# detect-UHF.net
KiCad netlist of a schematic drawn in EAGLE
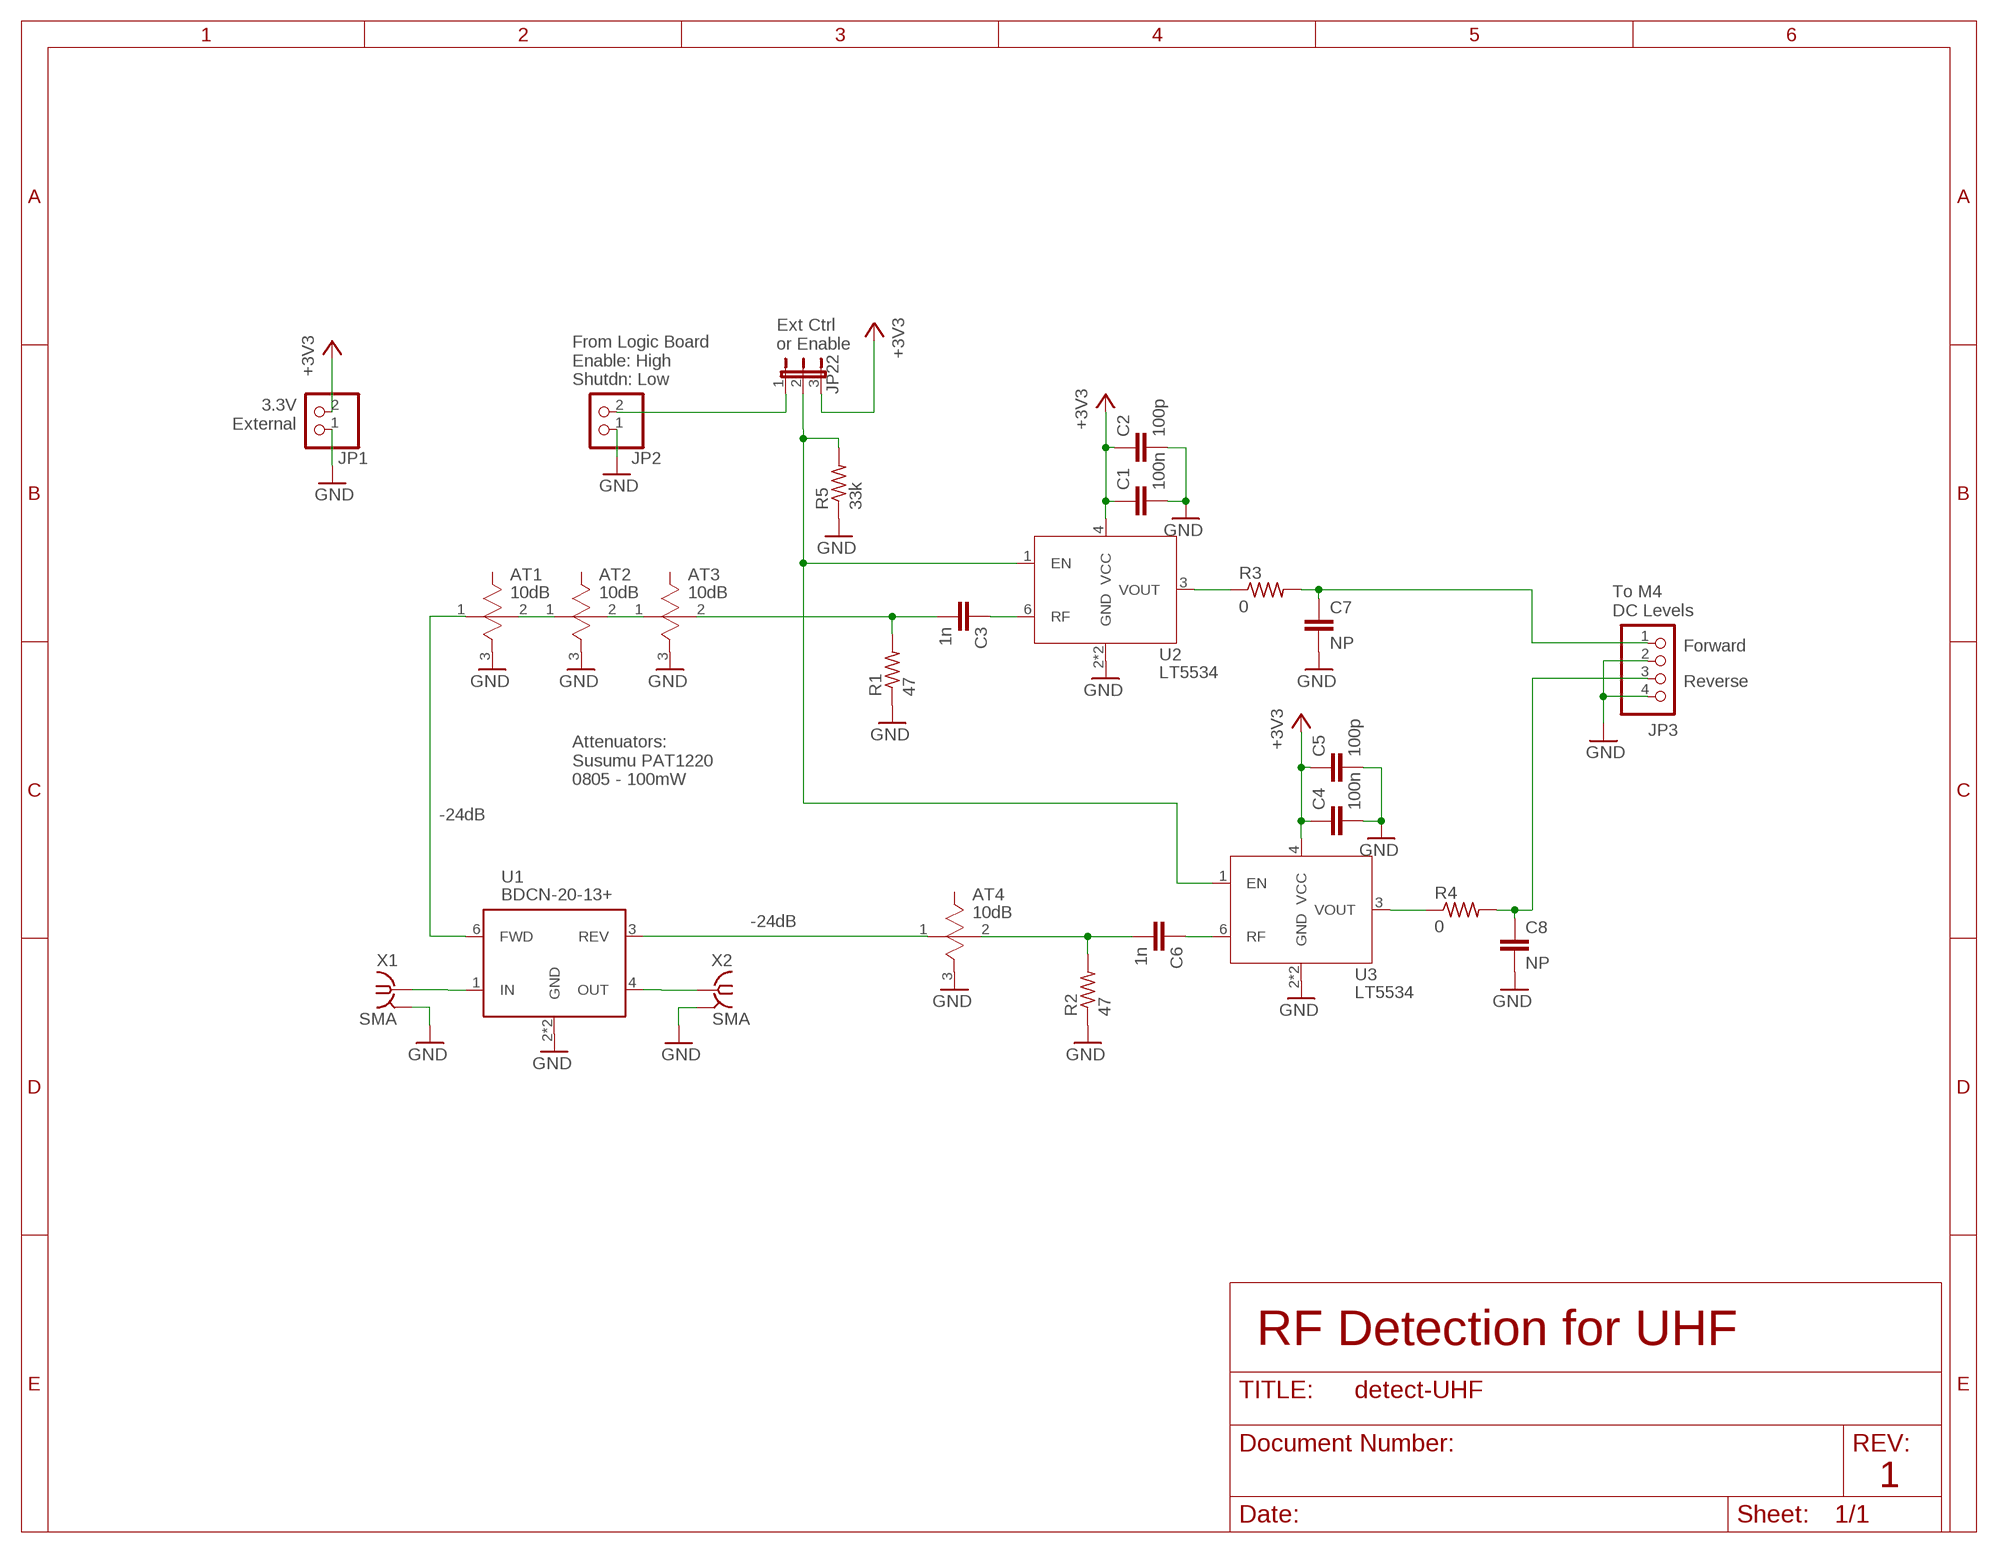
[diagram p0: schematic, sheet 1]

(export (version "E")
  (design (tool "Eeschema 10.0.6"))
  (components
    (comp (ref "AT1")
      (value "10dB")
      (footprint "eagle-import:PAT1220")
      (libsource (lib "eagle-import") (part "PAT1220"))
    )
    (comp (ref "AT2")
      (value "10dB")
      (footprint "eagle-import:PAT1220")
      (libsource (lib "eagle-import") (part "PAT1220"))
    )
    (comp (ref "AT3")
      (value "10dB")
      (footprint "eagle-import:PAT1220")
      (libsource (lib "eagle-import") (part "PAT1220"))
    )
    (comp (ref "AT4")
      (value "10dB")
      (footprint "eagle-import:PAT1220")
      (libsource (lib "eagle-import") (part "PAT1220"))
    )
    (comp (ref "C1")
      (value "100n")
      (footprint "eagle-import:.0603-B-NOSILK")
      (libsource (lib "eagle-import") (part "C-EU0603-B-NOSILK"))
    )
    (comp (ref "C2")
      (value "100p")
      (footprint "eagle-import:.0603-B-NOSILK")
      (libsource (lib "eagle-import") (part "C-EU0603-B-NOSILK"))
    )
    (comp (ref "C3")
      (value "1n")
      (footprint "eagle-import:.0402-B-NOSILK")
      (libsource (lib "eagle-import") (part "C-EU0402-B-NOSILK"))
    )
    (comp (ref "C4")
      (value "100n")
      (footprint "eagle-import:.0603-B-NOSILK")
      (libsource (lib "eagle-import") (part "C-EU0603-B-NOSILK"))
    )
    (comp (ref "C5")
      (value "100p")
      (footprint "eagle-import:.0603-B-NOSILK")
      (libsource (lib "eagle-import") (part "C-EU0603-B-NOSILK"))
    )
    (comp (ref "C6")
      (value "1n")
      (footprint "eagle-import:.0402-B-NOSILK")
      (libsource (lib "eagle-import") (part "C-EU0402-B-NOSILK"))
    )
    (comp (ref "C7")
      (value "NP")
      (footprint "eagle-import:.0603-B-NOSILK")
      (libsource (lib "eagle-import") (part "C-EU0603-B-NOSILK"))
    )
    (comp (ref "C8")
      (value "NP")
      (footprint "eagle-import:.0603-B-NOSILK")
      (libsource (lib "eagle-import") (part "C-EU0603-B-NOSILK"))
    )
    (comp (ref "JP1")
      (value "PINHD-1X2")
      (footprint "eagle-import:1X02")
      (libsource (lib "eagle-import") (part "PINHD-1X2"))
    )
    (comp (ref "JP2")
      (value "PINHD-1X2")
      (footprint "eagle-import:1X02")
      (libsource (lib "eagle-import") (part "PINHD-1X2"))
    )
    (comp (ref "JP3")
      (value "PINHD-1X4")
      (footprint "eagle-import:1X04")
      (libsource (lib "eagle-import") (part "PINHD-1X4"))
    )
    (comp (ref "JP22")
      (value "JP2E")
      (footprint "eagle-import:JP2")
      (libsource (lib "eagle-import") (part "JP2E"))
    )
    (comp (ref "R1")
      (value "47")
      (footprint "eagle-import:.0402-B-NOSILK")
      (libsource (lib "eagle-import") (part "R-US_0402-B-NOSILK"))
    )
    (comp (ref "R2")
      (value "47")
      (footprint "eagle-import:.0402-B-NOSILK")
      (libsource (lib "eagle-import") (part "R-US_0402-B-NOSILK"))
    )
    (comp (ref "R3")
      (value "0")
      (footprint "eagle-import:.0603-B-NOSILK")
      (libsource (lib "eagle-import") (part "R-US_0603-B-NOSILK"))
    )
    (comp (ref "R4")
      (value "0")
      (footprint "eagle-import:.0603-B-NOSILK")
      (libsource (lib "eagle-import") (part "R-US_0603-B-NOSILK"))
    )
    (comp (ref "R5")
      (value "33k")
      (footprint "eagle-import:.0402-B-NOSILK")
      (libsource (lib "eagle-import") (part "R-US_0402-B-NOSILK"))
    )
    (comp (ref "U1")
      (value "BDCN-20-13+")
      (footprint "eagle-import:BDCN-20-13+")
      (libsource (lib "eagle-import") (part "BDCN-20-13+"))
    )
    (comp (ref "U2")
      (value "LT5534")
      (footprint "eagle-import:SC70")
      (libsource (lib "eagle-import") (part "LT5534"))
    )
    (comp (ref "U3")
      (value "LT5534")
      (footprint "eagle-import:SC70")
      (libsource (lib "eagle-import") (part "LT5534"))
    )
    (comp (ref "X1")
      (value "SMA")
      (footprint "eagle-import:J502-ND-142-0701-801_806")
      (fields (field (name "MF") "JOHNSON COMPONENTS") (field (name "MPN") "142-0701-801"))
      (libsource (lib "eagle-import") (part "SMA-142-0701-801/806"))
    )
    (comp (ref "X2")
      (value "SMA")
      (footprint "eagle-import:J502-ND-142-0701-801_806")
      (fields (field (name "MF") "JOHNSON COMPONENTS") (field (name "MPN") "142-0701-801"))
      (libsource (lib "eagle-import") (part "SMA-142-0701-801/806"))
    )
  )
  (nets
    (net (code "1") (name "+3V3") (class "Default")
      (node (ref "C1") (pin "1") (pinfunction "1_1") (pintype "passive"))
      (node (ref "C2") (pin "1") (pinfunction "1_1") (pintype "passive"))
      (node (ref "C4") (pin "1") (pinfunction "1_1") (pintype "passive"))
      (node (ref "C5") (pin "1") (pinfunction "1_1") (pintype "passive"))
      (node (ref "JP1") (pin "2") (pinfunction "2_2") (pintype "passive"))
      (node (ref "JP22") (pin "3") (pinfunction "3_3") (pintype "passive"))
      (node (ref "U2") (pin "4") (pinfunction "VCC_4") (pintype "power_in"))
      (node (ref "U3") (pin "4") (pinfunction "VCC_4") (pintype "power_in"))
    )
    (net (code "2") (name "GND") (class "Default")
      (node (ref "AT1") (pin "3") (pinfunction "GND_3") (pintype "power_in"))
      (node (ref "AT2") (pin "3") (pinfunction "GND_3") (pintype "power_in"))
      (node (ref "AT3") (pin "3") (pinfunction "GND_3") (pintype "power_in"))
      (node (ref "AT4") (pin "3") (pinfunction "GND_3") (pintype "power_in"))
      (node (ref "C1") (pin "2") (pinfunction "2_2") (pintype "passive"))
      (node (ref "C2") (pin "2") (pinfunction "2_2") (pintype "passive"))
      (node (ref "C4") (pin "2") (pinfunction "2_2") (pintype "passive"))
      (node (ref "C5") (pin "2") (pinfunction "2_2") (pintype "passive"))
      (node (ref "C7") (pin "2") (pinfunction "2_2") (pintype "passive"))
      (node (ref "C8") (pin "2") (pinfunction "2_2") (pintype "passive"))
      (node (ref "JP1") (pin "1") (pinfunction "1_1") (pintype "passive"))
      (node (ref "JP2") (pin "1") (pinfunction "1_1") (pintype "passive"))
      (node (ref "JP3") (pin "2") (pinfunction "2_2") (pintype "passive"))
      (node (ref "JP3") (pin "4") (pinfunction "4_4") (pintype "passive"))
      (node (ref "R1") (pin "1") (pinfunction "1_1") (pintype "passive"))
      (node (ref "R2") (pin "1") (pinfunction "1_1") (pintype "passive"))
      (node (ref "R5") (pin "1") (pinfunction "1_1") (pintype "passive"))
      (node (ref "U1") (pin "2") (pinfunction "GND_2") (pintype "power_in"))
      (node (ref "U1") (pin "5") (pinfunction "GND_5") (pintype "power_in"))
      (node (ref "U2") (pin "2") (pinfunction "GND_2") (pintype "power_in"))
      (node (ref "U2") (pin "5") (pinfunction "GND_5") (pintype "power_in"))
      (node (ref "U3") (pin "2") (pinfunction "GND_2") (pintype "power_in"))
      (node (ref "U3") (pin "5") (pinfunction "GND_5") (pintype "power_in"))
      (node (ref "X1") (pin "G@1") (pinfunction "2_G@1") (pintype "passive"))
      (node (ref "X1") (pin "G@2") (pinfunction "2_G@2") (pintype "passive"))
      (node (ref "X1") (pin "G@3") (pinfunction "2_G@3") (pintype "passive"))
      (node (ref "X1") (pin "G@4") (pinfunction "2_G@4") (pintype "passive"))
      (node (ref "X2") (pin "G@1") (pinfunction "2_G@1") (pintype "passive"))
      (node (ref "X2") (pin "G@2") (pinfunction "2_G@2") (pintype "passive"))
      (node (ref "X2") (pin "G@3") (pinfunction "2_G@3") (pintype "passive"))
      (node (ref "X2") (pin "G@4") (pinfunction "2_G@4") (pintype "passive"))
    )
    (net (code "3") (name "Net-(AT1-Pad2)") (class "Default")
      (node (ref "AT1") (pin "2") (pinfunction "2_2") (pintype "bidirectional"))
      (node (ref "AT2") (pin "1") (pinfunction "1_1") (pintype "bidirectional"))
    )
    (net (code "4") (name "Net-(AT2-Pad2)") (class "Default")
      (node (ref "AT2") (pin "2") (pinfunction "2_2") (pintype "bidirectional"))
      (node (ref "AT3") (pin "1") (pinfunction "1_1") (pintype "bidirectional"))
    )
    (net (code "5") (name "Net-(AT3-Pad2)") (class "Default")
      (node (ref "AT3") (pin "2") (pinfunction "2_2") (pintype "bidirectional"))
      (node (ref "C3") (pin "2") (pinfunction "2_2") (pintype "passive"))
      (node (ref "R1") (pin "2") (pinfunction "2_2") (pintype "passive"))
    )
    (net (code "6") (name "Net-(AT4-Pad2)") (class "Default")
      (node (ref "AT4") (pin "2") (pinfunction "2_2") (pintype "bidirectional"))
      (node (ref "C6") (pin "2") (pinfunction "2_2") (pintype "passive"))
      (node (ref "R2") (pin "2") (pinfunction "2_2") (pintype "passive"))
    )
    (net (code "7") (name "Net-(C7-Pad1)") (class "Default")
      (node (ref "C7") (pin "1") (pinfunction "1_1") (pintype "passive"))
      (node (ref "JP3") (pin "1") (pinfunction "1_1") (pintype "passive"))
      (node (ref "R3") (pin "2") (pinfunction "2_2") (pintype "passive"))
    )
    (net (code "8") (name "Net-(C8-Pad1)") (class "Default")
      (node (ref "C8") (pin "1") (pinfunction "1_1") (pintype "passive"))
      (node (ref "JP3") (pin "3") (pinfunction "3_3") (pintype "passive"))
      (node (ref "R4") (pin "2") (pinfunction "2_2") (pintype "passive"))
    )
    (net (code "9") (name "Net-(JP2-Pad2)") (class "Default")
      (node (ref "JP2") (pin "2") (pinfunction "2_2") (pintype "passive"))
      (node (ref "JP22") (pin "1") (pinfunction "1_1") (pintype "passive"))
    )
    (net (code "10") (name "Net-(U1-FWD)") (class "Default")
      (node (ref "AT1") (pin "1") (pinfunction "1_1") (pintype "bidirectional"))
      (node (ref "U1") (pin "6") (pinfunction "FWD_6") (pintype "output"))
    )
    (net (code "11") (name "Net-(U1-IN)") (class "Default")
      (node (ref "U1") (pin "1") (pinfunction "IN_1") (pintype "input"))
      (node (ref "X1") (pin "1") (pinfunction "1_1") (pintype "passive"))
    )
    (net (code "12") (name "Net-(U1-OUT)") (class "Default")
      (node (ref "U1") (pin "4") (pinfunction "OUT_4") (pintype "output"))
      (node (ref "X2") (pin "1") (pinfunction "1_1") (pintype "passive"))
    )
    (net (code "13") (name "Net-(U1-REV)") (class "Default")
      (node (ref "AT4") (pin "1") (pinfunction "1_1") (pintype "bidirectional"))
      (node (ref "U1") (pin "3") (pinfunction "REV_3") (pintype "output"))
    )
    (net (code "14") (name "Net-(U2-EN)") (class "Default")
      (node (ref "JP22") (pin "2") (pinfunction "2_2") (pintype "passive"))
      (node (ref "R5") (pin "2") (pinfunction "2_2") (pintype "passive"))
      (node (ref "U2") (pin "1") (pinfunction "EN_1") (pintype "input"))
      (node (ref "U3") (pin "1") (pinfunction "EN_1") (pintype "input"))
    )
    (net (code "15") (name "Net-(U2-RF)") (class "Default")
      (node (ref "C3") (pin "1") (pinfunction "1_1") (pintype "passive"))
      (node (ref "U2") (pin "6") (pinfunction "RF_6") (pintype "input"))
    )
    (net (code "16") (name "Net-(U2-VOUT)") (class "Default")
      (node (ref "R3") (pin "1") (pinfunction "1_1") (pintype "passive"))
      (node (ref "U2") (pin "3") (pinfunction "VOUT_3") (pintype "output"))
    )
    (net (code "17") (name "Net-(U3-RF)") (class "Default")
      (node (ref "C6") (pin "1") (pinfunction "1_1") (pintype "passive"))
      (node (ref "U3") (pin "6") (pinfunction "RF_6") (pintype "input"))
    )
    (net (code "18") (name "Net-(U3-VOUT)") (class "Default")
      (node (ref "R4") (pin "1") (pinfunction "1_1") (pintype "passive"))
      (node (ref "U3") (pin "3") (pinfunction "VOUT_3") (pintype "output"))
    )
  )
)
